# MCU.net
KiCad netlist of a schematic drawn in Altium Designer
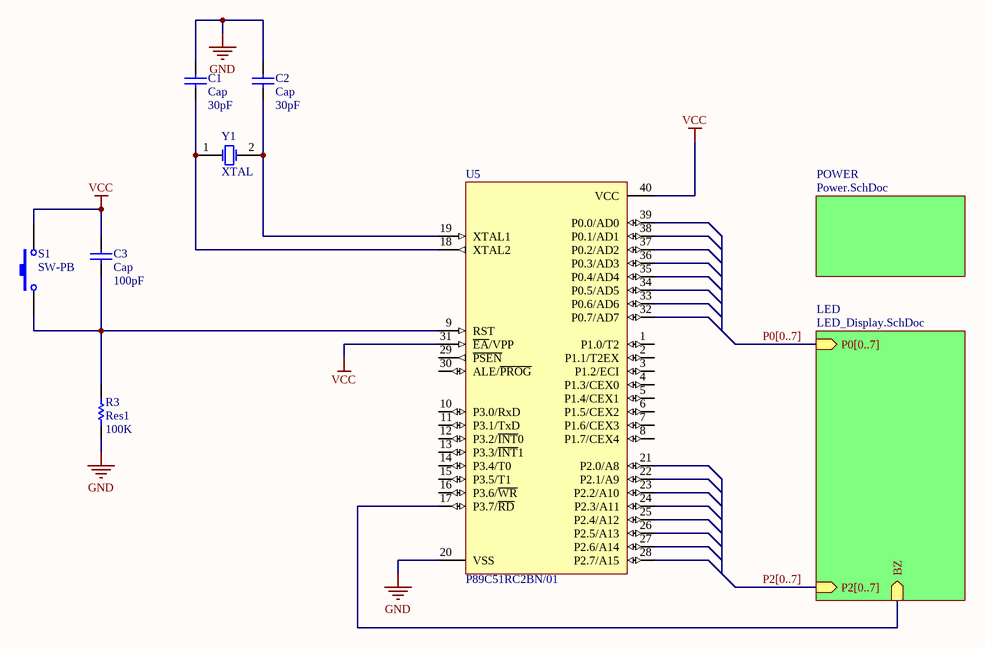
[diagram p0: MCU.SchDoc]

(export (version "E")
  (design (tool "Eeschema 10.0.6"))
  (components
    (comp (ref "C1")
      (value "Cap")
      (footprint "RAD-0.3")
      (description "Capacitor")
      (fields (field (name "ALTIUM_VALUE") "30pF") (field (name "PUBLISHER") "Altium Limited"))
      (libsource (lib "Chap-7-实践题(1)") (part "Cap"))
    )
    (comp (ref "C2")
      (value "Cap")
      (footprint "RAD-0.3")
      (description "Capacitor")
      (fields (field (name "ALTIUM_VALUE") "30pF") (field (name "PUBLISHER") "Altium Limited"))
      (libsource (lib "Chap-7-实践题(1)") (part "Cap"))
    )
    (comp (ref "C3")
      (value "Cap")
      (footprint "RAD-0.3")
      (description "Capacitor")
      (fields (field (name "ALTIUM_VALUE") "100pF") (field (name "PUBLISHER") "Altium Limited"))
      (libsource (lib "Chap-7-实践题(1)") (part "Cap"))
    )
    (comp (ref "R3")
      (value "Res1")
      (footprint "AXIAL-0.3")
      (description "Resistor")
      (fields (field (name "ALTIUM_VALUE") "100K") (field (name "PUBLISHER") "Altium Limited"))
      (libsource (lib "Chap-7-实践题(1)") (part "Res1"))
    )
    (comp (ref "S1")
      (value "SW-PB")
      (footprint "SPST-2")
      (description "Switch")
      (fields (field (name "PUBLISHER") "Altium Limited"))
      (libsource (lib "Chap-7-实践题(1)") (part "SW-PB"))
    )
    (comp (ref "U5")
      (value "P89C51RC2BN/01")
      (footprint "SOT129-1")
      (description "80C51 8-Bit Flash Microcontroller Family, 32 kB ISP/IAP Flash with 512 B RAM.")
      (fields (field (name "PUBLISHER") "Altium Limited"))
      (libsource (lib "Chap-7-实践题(1)") (part "P89C51RC2BN/01"))
    )
    (comp (ref "Y1")
      (value "XTAL")
      (footprint "R38")
      (description "Crystal Oscillator")
      (fields (field (name "PUBLISHER") "Altium Limited"))
      (libsource (lib "Chap-7-实践题(1)") (part "XTAL"))
    )
  )
  (nets
    (net (code "17") (name "/BZ") (class "Default")
      (node (ref "U5") (pin "17") (pinfunction "P3.7/~{RD}_17") (pintype "bidirectional"))
    )
    (net (code "20") (name "GND") (class "Default")
      (node (ref "C1") (pin "2") (pinfunction "2_2") (pintype "passive"))
      (node (ref "C2") (pin "2") (pinfunction "2_2") (pintype "passive"))
      (node (ref "R3") (pin "1") (pinfunction "1_1") (pintype "passive"))
      (node (ref "U5") (pin "20") (pinfunction "VSS_20") (pintype "power_in"))
    )
    (net (code "21") (name "Net-(U5-RST)") (class "Default")
      (node (ref "C3") (pin "1") (pinfunction "1_1") (pintype "passive"))
      (node (ref "R3") (pin "2") (pinfunction "2_2") (pintype "passive"))
      (node (ref "S1") (pin "1") (pinfunction "1_1") (pintype "passive"))
      (node (ref "U5") (pin "9") (pinfunction "RST_9") (pintype "input"))
    )
    (net (code "22") (name "Net-(U5-XTAL1)") (class "Default")
      (node (ref "C2") (pin "1") (pinfunction "1_1") (pintype "passive"))
      (node (ref "U5") (pin "19") (pinfunction "XTAL1_19") (pintype "input"))
      (node (ref "Y1") (pin "2") (pinfunction "OSC2_2") (pintype "passive"))
    )
    (net (code "23") (name "Net-(U5-XTAL2)") (class "Default")
      (node (ref "C1") (pin "1") (pinfunction "1_1") (pintype "passive"))
      (node (ref "U5") (pin "18") (pinfunction "XTAL2_18") (pintype "output"))
      (node (ref "Y1") (pin "1") (pinfunction "OSC1_1") (pintype "passive"))
    )
    (net (code "24") (name "VCC") (class "Default")
      (node (ref "C3") (pin "2") (pinfunction "2_2") (pintype "passive"))
      (node (ref "S1") (pin "2") (pinfunction "2_2") (pintype "passive"))
      (node (ref "U5") (pin "31") (pinfunction "~{EA}/VPP_31") (pintype "input"))
      (node (ref "U5") (pin "40") (pinfunction "VCC_40") (pintype "power_in"))
    )
    (net (code "25") (name "unconnected-(U5-ALE{slash}~{PROG}-Pad30)") (class "Default")
      (node (ref "U5") (pin "30") (pinfunction "ALE/~{PROG}_30") (pintype "bidirectional"))
    )
    (net (code "26") (name "unconnected-(U5-P0.0{slash}AD0-Pad39)") (class "Default")
      (node (ref "U5") (pin "39") (pinfunction "P0.0/AD0_39") (pintype "bidirectional"))
    )
    (net (code "27") (name "unconnected-(U5-P0.1{slash}AD1-Pad38)") (class "Default")
      (node (ref "U5") (pin "38") (pinfunction "P0.1/AD1_38") (pintype "bidirectional"))
    )
    (net (code "28") (name "unconnected-(U5-P0.2{slash}AD2-Pad37)") (class "Default")
      (node (ref "U5") (pin "37") (pinfunction "P0.2/AD2_37") (pintype "bidirectional"))
    )
    (net (code "29") (name "unconnected-(U5-P0.3{slash}AD3-Pad36)") (class "Default")
      (node (ref "U5") (pin "36") (pinfunction "P0.3/AD3_36") (pintype "bidirectional"))
    )
    (net (code "30") (name "unconnected-(U5-P0.4{slash}AD4-Pad35)") (class "Default")
      (node (ref "U5") (pin "35") (pinfunction "P0.4/AD4_35") (pintype "bidirectional"))
    )
    (net (code "31") (name "unconnected-(U5-P0.5{slash}AD5-Pad34)") (class "Default")
      (node (ref "U5") (pin "34") (pinfunction "P0.5/AD5_34") (pintype "bidirectional"))
    )
    (net (code "32") (name "unconnected-(U5-P0.6{slash}AD6-Pad33)") (class "Default")
      (node (ref "U5") (pin "33") (pinfunction "P0.6/AD6_33") (pintype "bidirectional"))
    )
    (net (code "33") (name "unconnected-(U5-P0.7{slash}AD7-Pad32)") (class "Default")
      (node (ref "U5") (pin "32") (pinfunction "P0.7/AD7_32") (pintype "bidirectional"))
    )
    (net (code "34") (name "unconnected-(U5-P1.0{slash}T2-Pad1)") (class "Default")
      (node (ref "U5") (pin "1") (pinfunction "P1.0/T2_1") (pintype "bidirectional"))
    )
    (net (code "35") (name "unconnected-(U5-P1.1{slash}T2EX-Pad2)") (class "Default")
      (node (ref "U5") (pin "2") (pinfunction "P1.1/T2EX_2") (pintype "bidirectional"))
    )
    (net (code "36") (name "unconnected-(U5-P1.2{slash}ECI-Pad3)") (class "Default")
      (node (ref "U5") (pin "3") (pinfunction "P1.2/ECI_3") (pintype "bidirectional"))
    )
    (net (code "37") (name "unconnected-(U5-P1.3{slash}CEX0-Pad4)") (class "Default")
      (node (ref "U5") (pin "4") (pinfunction "P1.3/CEX0_4") (pintype "bidirectional"))
    )
    (net (code "38") (name "unconnected-(U5-P1.4{slash}CEX1-Pad5)") (class "Default")
      (node (ref "U5") (pin "5") (pinfunction "P1.4/CEX1_5") (pintype "bidirectional"))
    )
    (net (code "39") (name "unconnected-(U5-P1.5{slash}CEX2-Pad6)") (class "Default")
      (node (ref "U5") (pin "6") (pinfunction "P1.5/CEX2_6") (pintype "bidirectional"))
    )
    (net (code "40") (name "unconnected-(U5-P1.6{slash}CEX3-Pad7)") (class "Default")
      (node (ref "U5") (pin "7") (pinfunction "P1.6/CEX3_7") (pintype "bidirectional"))
    )
    (net (code "41") (name "unconnected-(U5-P1.7{slash}CEX4-Pad8)") (class "Default")
      (node (ref "U5") (pin "8") (pinfunction "P1.7/CEX4_8") (pintype "bidirectional"))
    )
    (net (code "42") (name "unconnected-(U5-P2.0{slash}A8-Pad21)") (class "Default")
      (node (ref "U5") (pin "21") (pinfunction "P2.0/A8_21") (pintype "bidirectional"))
    )
    (net (code "43") (name "unconnected-(U5-P2.1{slash}A9-Pad22)") (class "Default")
      (node (ref "U5") (pin "22") (pinfunction "P2.1/A9_22") (pintype "bidirectional"))
    )
    (net (code "44") (name "unconnected-(U5-P2.2{slash}A10-Pad23)") (class "Default")
      (node (ref "U5") (pin "23") (pinfunction "P2.2/A10_23") (pintype "bidirectional"))
    )
    (net (code "45") (name "unconnected-(U5-P2.3{slash}A11-Pad24)") (class "Default")
      (node (ref "U5") (pin "24") (pinfunction "P2.3/A11_24") (pintype "bidirectional"))
    )
    (net (code "46") (name "unconnected-(U5-P2.4{slash}A12-Pad25)") (class "Default")
      (node (ref "U5") (pin "25") (pinfunction "P2.4/A12_25") (pintype "bidirectional"))
    )
    (net (code "47") (name "unconnected-(U5-P2.5{slash}A13-Pad26)") (class "Default")
      (node (ref "U5") (pin "26") (pinfunction "P2.5/A13_26") (pintype "bidirectional"))
    )
    (net (code "48") (name "unconnected-(U5-P2.6{slash}A14-Pad27)") (class "Default")
      (node (ref "U5") (pin "27") (pinfunction "P2.6/A14_27") (pintype "bidirectional"))
    )
    (net (code "49") (name "unconnected-(U5-P2.7{slash}A15-Pad28)") (class "Default")
      (node (ref "U5") (pin "28") (pinfunction "P2.7/A15_28") (pintype "bidirectional"))
    )
    (net (code "50") (name "unconnected-(U5-P3.0{slash}RxD-Pad10)") (class "Default")
      (node (ref "U5") (pin "10") (pinfunction "P3.0/RxD_10") (pintype "bidirectional"))
    )
    (net (code "51") (name "unconnected-(U5-P3.1{slash}TxD-Pad11)") (class "Default")
      (node (ref "U5") (pin "11") (pinfunction "P3.1/TxD_11") (pintype "bidirectional"))
    )
    (net (code "52") (name "unconnected-(U5-P3.2{slash}~{INT}0-Pad12)") (class "Default")
      (node (ref "U5") (pin "12") (pinfunction "P3.2/~{INT}0_12") (pintype "bidirectional"))
    )
    (net (code "53") (name "unconnected-(U5-P3.3{slash}~{INT}1-Pad13)") (class "Default")
      (node (ref "U5") (pin "13") (pinfunction "P3.3/~{INT}1_13") (pintype "bidirectional"))
    )
    (net (code "54") (name "unconnected-(U5-P3.4{slash}T0-Pad14)") (class "Default")
      (node (ref "U5") (pin "14") (pinfunction "P3.4/T0_14") (pintype "bidirectional"))
    )
    (net (code "55") (name "unconnected-(U5-P3.5{slash}T1-Pad15)") (class "Default")
      (node (ref "U5") (pin "15") (pinfunction "P3.5/T1_15") (pintype "bidirectional"))
    )
    (net (code "56") (name "unconnected-(U5-P3.6{slash}~{WR}-Pad16)") (class "Default")
      (node (ref "U5") (pin "16") (pinfunction "P3.6/~{WR}_16") (pintype "bidirectional"))
    )
    (net (code "57") (name "unconnected-(U5-~{PSEN}-Pad29)") (class "Default")
      (node (ref "U5") (pin "29") (pinfunction "~{PSEN}_29") (pintype "output"))
    )
  )
)
